# BLE-LORA-Relay-30dbm-v1-1.net
KiCad netlist of a schematic drawn in EAGLE
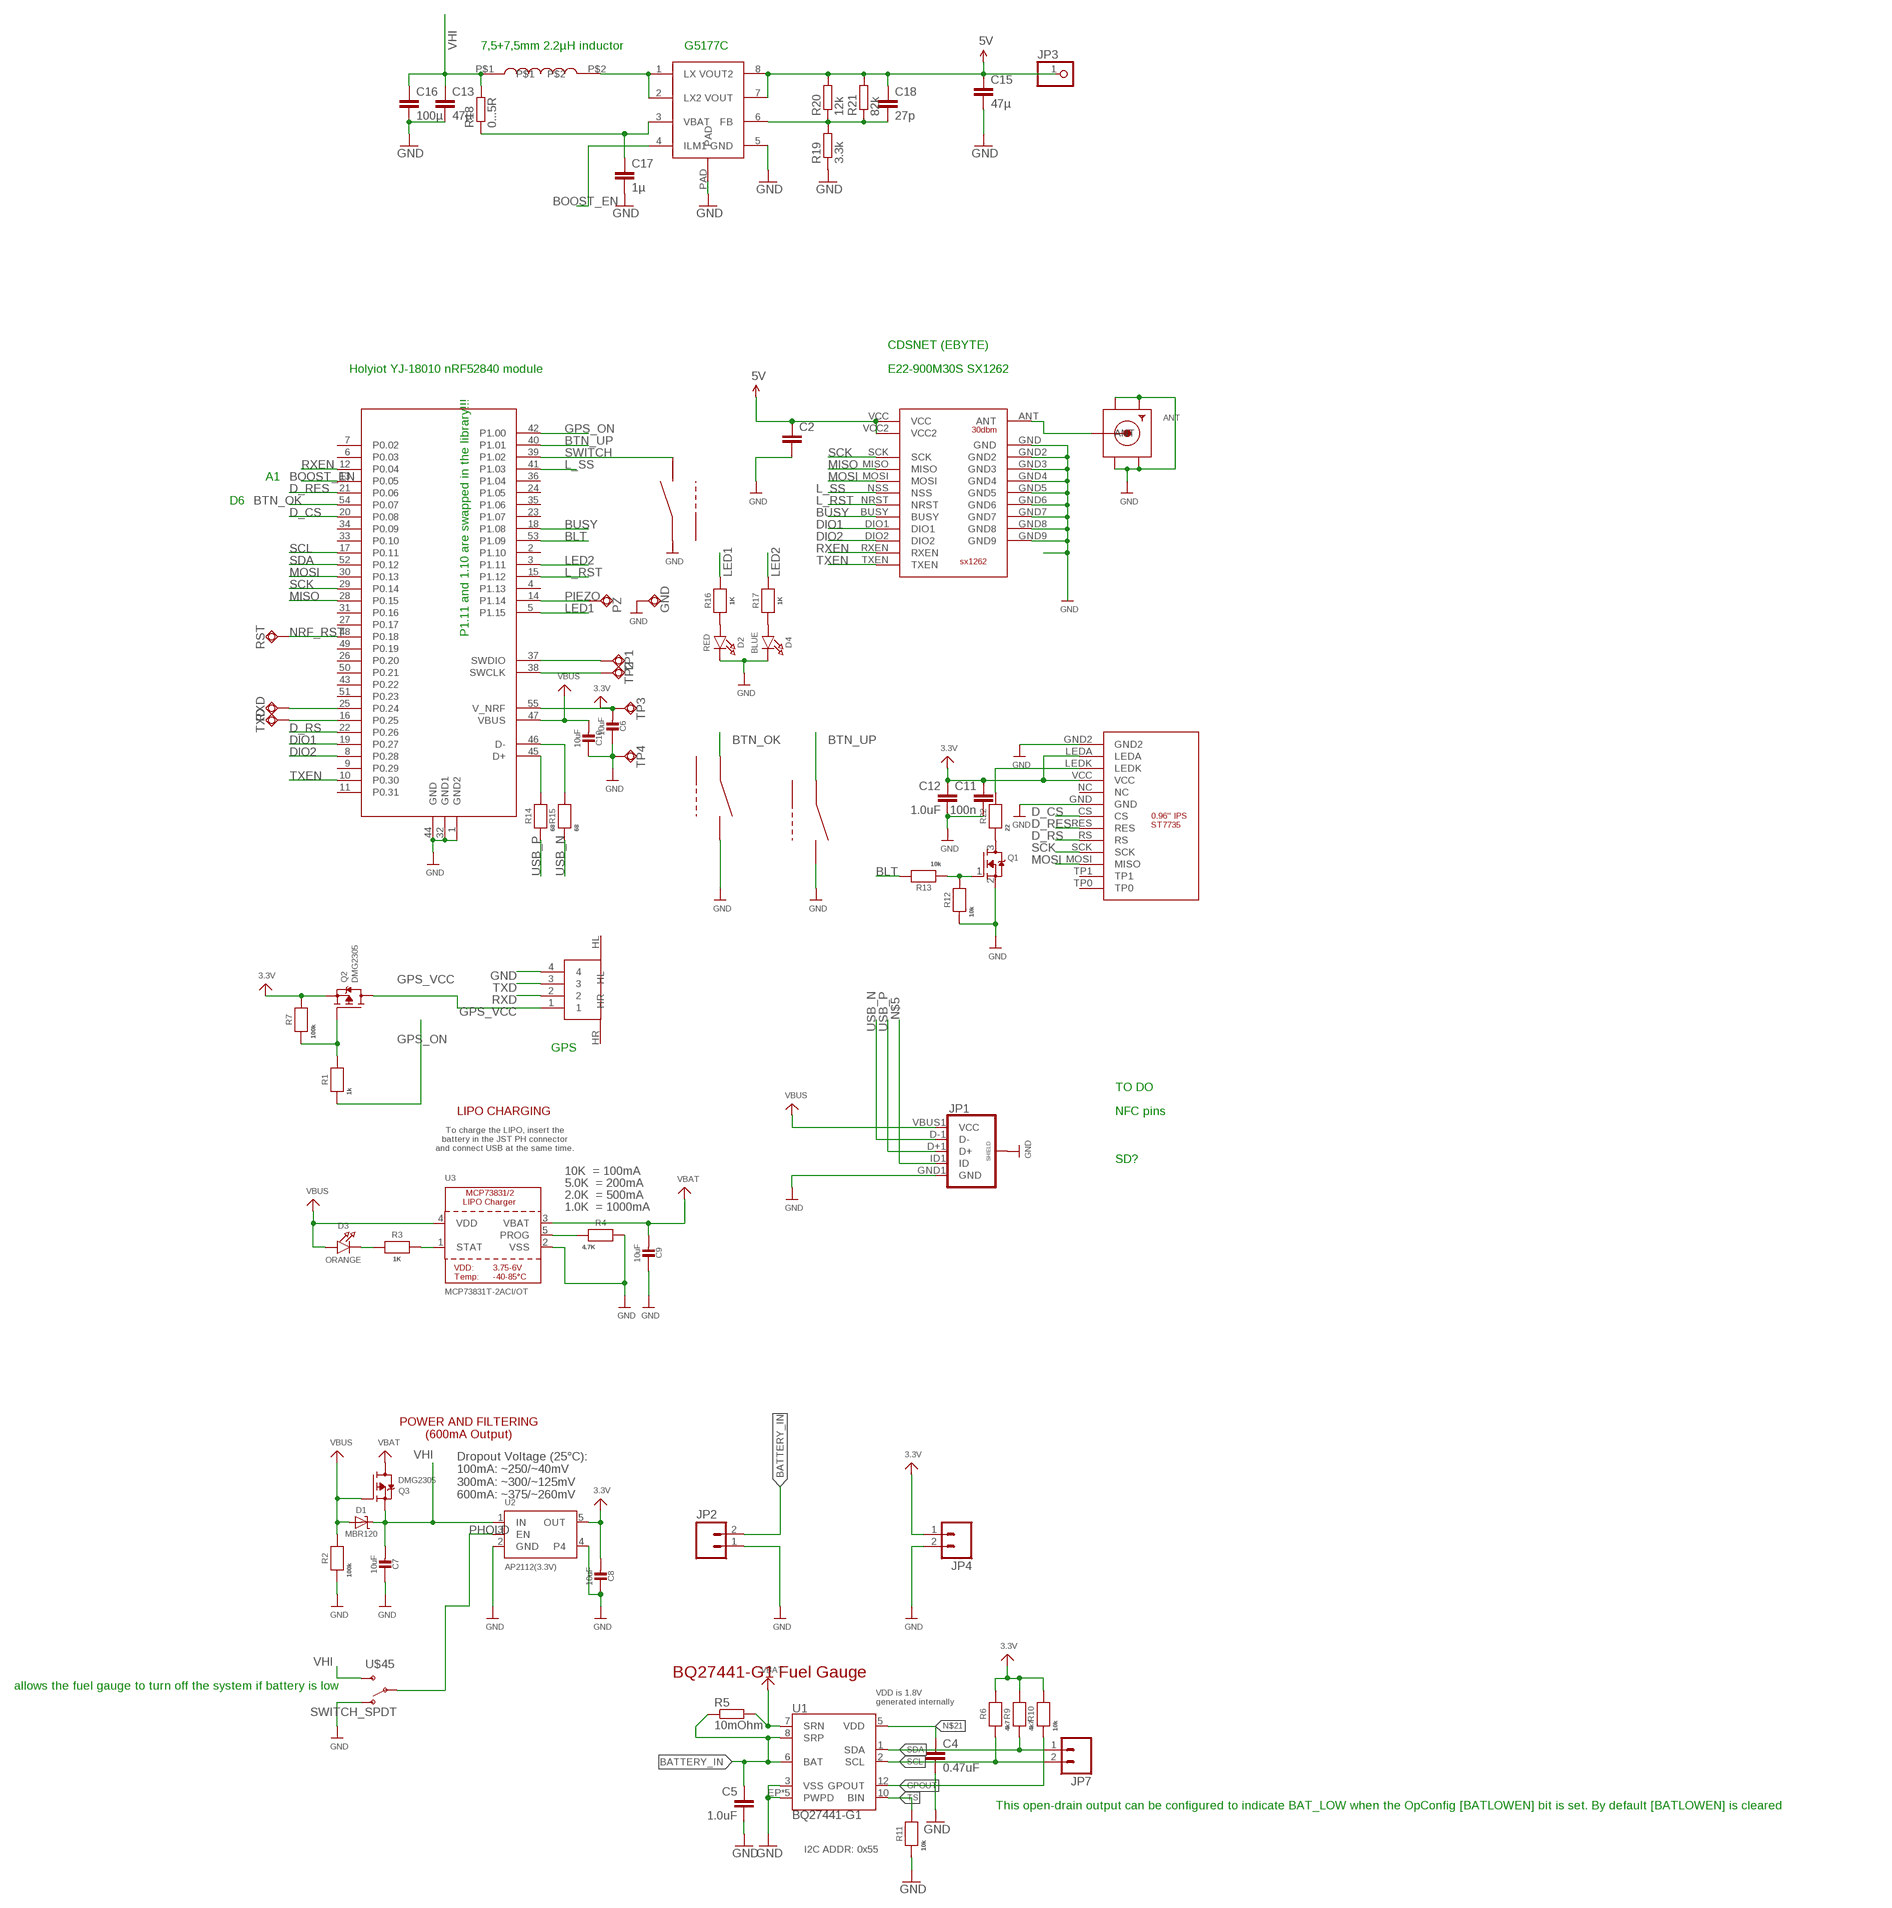
[diagram p0: schematic, sheet 1]

(export (version "E")
  (design (tool "Eeschema 10.0.6"))
  (components
    (comp (ref "ANT")
      (value "SMACONNECTOR_EDGE")
      (footprint "eagle-import:SMA_EDGELAUNCH")
      (libsource (lib "eagle-import") (part "SMACONNECTOR_EDGE"))
    )
    (comp (ref "C2")
      (value "C-EUC1206")
      (footprint "eagle-import:C1206")
      (libsource (lib "eagle-import") (part "C-EUC1206"))
    )
    (comp (ref "C4")
      (value "0.47uF")
      (footprint "eagle-import:0603-CAP")
      (libsource (lib "eagle-import") (part "CAP0603-CAP"))
    )
    (comp (ref "C5")
      (value "1.0uF")
      (footprint "eagle-import:0603-CAP")
      (libsource (lib "eagle-import") (part "1.0UF-16V-10%(0603)"))
    )
    (comp (ref "C6")
      (value "10uF")
      (footprint "eagle-import:0805-NO")
      (libsource (lib "eagle-import") (part "CAP_CERAMIC0805-NOOUTLINE"))
    )
    (comp (ref "C7")
      (value "10uF")
      (footprint "eagle-import:0805-NO")
      (libsource (lib "eagle-import") (part "CAP_CERAMIC0805-NOOUTLINE"))
    )
    (comp (ref "C8")
      (value "10uF")
      (footprint "eagle-import:0805-NO")
      (libsource (lib "eagle-import") (part "CAP_CERAMIC0805-NOOUTLINE"))
    )
    (comp (ref "C9")
      (value "10uF")
      (footprint "eagle-import:0805-NO")
      (libsource (lib "eagle-import") (part "CAP_CERAMIC0805-NOOUTLINE"))
    )
    (comp (ref "C10")
      (value "10uF")
      (footprint "eagle-import:0805-NO")
      (libsource (lib "eagle-import") (part "CAP_CERAMIC0805-NOOUTLINE"))
    )
    (comp (ref "C11")
      (value "100n")
      (footprint "eagle-import:0603-CAP")
      (libsource (lib "eagle-import") (part "1.0UF-16V-10%(0603)"))
    )
    (comp (ref "C12")
      (value "1.0uF")
      (footprint "eagle-import:0603-CAP")
      (libsource (lib "eagle-import") (part "1.0UF-16V-10%(0603)"))
    )
    (comp (ref "C13")
      (value "47µ")
      (footprint "eagle-import:C0805")
      (libsource (lib "eagle-import") (part "C-EUC0805"))
    )
    (comp (ref "C15")
      (value "47µ")
      (footprint "eagle-import:C0805")
      (libsource (lib "eagle-import") (part "C-EUC0805"))
    )
    (comp (ref "C16")
      (value "100µ")
      (footprint "eagle-import:C1206")
      (libsource (lib "eagle-import") (part "C-EUC1206"))
    )
    (comp (ref "C17")
      (value "1µ")
      (footprint "eagle-import:C0603")
      (libsource (lib "eagle-import") (part "C-EUC0603"))
    )
    (comp (ref "C18")
      (value "27p")
      (footprint "eagle-import:C0603")
      (libsource (lib "eagle-import") (part "C-EUC0603"))
    )
    (comp (ref "D1")
      (value "MBR120")
      (footprint "eagle-import:SOD-123")
      (libsource (lib "eagle-import") (part "DIODE-SCHOTTKYSOD-123"))
    )
    (comp (ref "D2")
      (value "RED")
      (footprint "eagle-import:CHIPLED_0805_NOOUTLINE")
      (libsource (lib "eagle-import") (part "LED0805_NOOUTLINE"))
    )
    (comp (ref "D3")
      (value "ORANGE")
      (footprint "eagle-import:CHIPLED_0805_NOOUTLINE")
      (libsource (lib "eagle-import") (part "LED0805_NOOUTLINE"))
    )
    (comp (ref "D4")
      (value "BLUE")
      (footprint "eagle-import:CHIPLED_0805_NOOUTLINE")
      (libsource (lib "eagle-import") (part "LED0805_NOOUTLINE"))
    )
    (comp (ref "DWN")
      (value "LS12T2")
      (footprint "eagle-import:LS12T2")
      (libsource (lib "eagle-import") (part "LS12T2"))
    )
    (comp (ref "DWN1")
      (value "LS12T2")
      (footprint "eagle-import:LS12T2")
      (libsource (lib "eagle-import") (part "LS12T2"))
    )
    (comp (ref "DWN2")
      (value "LS12T2")
      (footprint "eagle-import:LS12T2")
      (libsource (lib "eagle-import") (part "LS12T2"))
    )
    (comp (ref "GND")
      (value "TPSQTP13R")
      (footprint "eagle-import:TP13R")
      (libsource (lib "eagle-import") (part "TPSQTP13R"))
    )
    (comp (ref "JP1")
      (value "USB_MICROB_PLUGCONN-11752")
      (footprint "eagle-import:USB-B-MICRO-SMD_V03")
      (libsource (lib "eagle-import") (part "USB_MICROB_PLUGCONN-11752"))
    )
    (comp (ref "JP2")
      (value "M02PTH")
      (footprint "eagle-import:1X02")
      (libsource (lib "eagle-import") (part "M02PTH"))
    )
    (comp (ref "JP3")
      (value "PINHD-1X1")
      (footprint "eagle-import:1X01")
      (libsource (lib "eagle-import") (part "PINHD-1X1"))
    )
    (comp (ref "JP4")
      (value "M02PTH")
      (footprint "eagle-import:1X02")
      (libsource (lib "eagle-import") (part "M02PTH"))
    )
    (comp (ref "JP7")
      (value "M02PTH")
      (footprint "eagle-import:1X02")
      (libsource (lib "eagle-import") (part "M02PTH"))
    )
    (comp (ref "PZ")
      (value "TPSQTP13R")
      (footprint "eagle-import:TP13R")
      (libsource (lib "eagle-import") (part "TPSQTP13R"))
    )
    (comp (ref "Q1")
      (value "MOSFET-NREFLOW")
      (footprint "eagle-import:SOT23")
      (libsource (lib "eagle-import") (part "MOSFET-NREFLOW"))
    )
    (comp (ref "Q2")
      (value "DMG2305")
      (footprint "eagle-import:SOT23-R")
      (libsource (lib "eagle-import") (part "MOSFET-P"))
    )
    (comp (ref "Q3")
      (value "DMG2305")
      (footprint "eagle-import:SOT23-R")
      (libsource (lib "eagle-import") (part "MOSFET-P"))
    )
    (comp (ref "R1")
      (value "1k")
      (footprint "eagle-import:0603-NO")
      (libsource (lib "eagle-import") (part "RESISTOR_0603_NOOUT"))
    )
    (comp (ref "R2")
      (value "100k")
      (footprint "eagle-import:0603-NO")
      (libsource (lib "eagle-import") (part "RESISTOR_0603_NOOUT"))
    )
    (comp (ref "R3")
      (value "1K")
      (footprint "eagle-import:0603-NO")
      (libsource (lib "eagle-import") (part "RESISTOR_0603_NOOUT"))
    )
    (comp (ref "R4")
      (value "4.7K")
      (footprint "eagle-import:0603-NO")
      (libsource (lib "eagle-import") (part "RESISTOR_0603_NOOUT"))
    )
    (comp (ref "R5")
      (value "10mOhm")
      (footprint "eagle-import:R0805")
      (libsource (lib "eagle-import") (part "R-EU_R0805"))
    )
    (comp (ref "R6")
      (value "4k7")
      (footprint "eagle-import:0603-NO")
      (libsource (lib "eagle-import") (part "RESISTOR_0603_NOOUT"))
    )
    (comp (ref "R7")
      (value "100k")
      (footprint "eagle-import:0603-NO")
      (libsource (lib "eagle-import") (part "RESISTOR_0603_NOOUT"))
    )
    (comp (ref "R9")
      (value "4k7")
      (footprint "eagle-import:0603-NO")
      (libsource (lib "eagle-import") (part "RESISTOR_0603_NOOUT"))
    )
    (comp (ref "R10")
      (value "10k")
      (footprint "eagle-import:0603-NO")
      (libsource (lib "eagle-import") (part "RESISTOR_0603_NOOUT"))
    )
    (comp (ref "R11")
      (value "10k")
      (footprint "eagle-import:0603-NO")
      (libsource (lib "eagle-import") (part "RESISTOR_0603_NOOUT"))
    )
    (comp (ref "R12")
      (value "10k")
      (footprint "eagle-import:0603-NO")
      (libsource (lib "eagle-import") (part "RESISTOR_0603_NOOUT"))
    )
    (comp (ref "R13")
      (value "10k")
      (footprint "eagle-import:0603-NO")
      (libsource (lib "eagle-import") (part "RESISTOR_0603_NOOUT"))
    )
    (comp (ref "R14")
      (value "68")
      (footprint "eagle-import:0603-NO")
      (libsource (lib "eagle-import") (part "RESISTOR_0603_NOOUT"))
    )
    (comp (ref "R15")
      (value "68")
      (footprint "eagle-import:0603-NO")
      (libsource (lib "eagle-import") (part "RESISTOR_0603_NOOUT"))
    )
    (comp (ref "R16")
      (value "1K")
      (footprint "eagle-import:0603-NO")
      (libsource (lib "eagle-import") (part "RESISTOR_0603_NOOUT"))
    )
    (comp (ref "R17")
      (value "1K")
      (footprint "eagle-import:0603-NO")
      (libsource (lib "eagle-import") (part "RESISTOR_0603_NOOUT"))
    )
    (comp (ref "R18")
      (value "0...5R")
      (footprint "eagle-import:R0603")
      (libsource (lib "eagle-import") (part "R-EU_R0603"))
    )
    (comp (ref "R19")
      (value "3.3k")
      (footprint "eagle-import:R0603")
      (libsource (lib "eagle-import") (part "R-EU_R0603"))
    )
    (comp (ref "R20")
      (value "12k")
      (footprint "eagle-import:R0603")
      (libsource (lib "eagle-import") (part "R-EU_R0603"))
    )
    (comp (ref "R21")
      (value "82k")
      (footprint "eagle-import:R0603")
      (libsource (lib "eagle-import") (part "R-EU_R0603"))
    )
    (comp (ref "R22")
      (value "22")
      (footprint "eagle-import:0603-NO")
      (libsource (lib "eagle-import") (part "RESISTOR_0603_NOOUT"))
    )
    (comp (ref "RST")
      (value "TPSQTP13R")
      (footprint "eagle-import:TP13R")
      (libsource (lib "eagle-import") (part "TPSQTP13R"))
    )
    (comp (ref "RXD")
      (value "TPSQTP13R")
      (footprint "eagle-import:TP13R")
      (libsource (lib "eagle-import") (part "TPSQTP13R"))
    )
    (comp (ref "TP1")
      (value "TPSQTP13R")
      (footprint "eagle-import:TP13R")
      (libsource (lib "eagle-import") (part "TPSQTP13R"))
    )
    (comp (ref "TP2")
      (value "TPSQTP13R")
      (footprint "eagle-import:TP13R")
      (libsource (lib "eagle-import") (part "TPSQTP13R"))
    )
    (comp (ref "TP3")
      (value "TPSQTP13R")
      (footprint "eagle-import:TP13R")
      (libsource (lib "eagle-import") (part "TPSQTP13R"))
    )
    (comp (ref "TP4")
      (value "TPSQTP13R")
      (footprint "eagle-import:TP13R")
      (libsource (lib "eagle-import") (part "TPSQTP13R"))
    )
    (comp (ref "TXD")
      (value "TPSQTP13R")
      (footprint "eagle-import:TP13R")
      (libsource (lib "eagle-import") (part "TPSQTP13R"))
    )
    (comp (ref "U$14")
      (value "NRF52840")
      (footprint "eagle-import:NRF52840MOD")
      (libsource (lib "eagle-import") (part "NRF52840"))
    )
    (comp (ref "U$15")
      (value "SX1262-30DBM")
      (footprint "eagle-import:SX1262-30DBM")
      (libsource (lib "eagle-import") (part "SX1262-30DBM"))
    )
    (comp (ref "U$16")
      (value "0.96_IPS")
      (footprint "eagle-import:0.96_IPS")
      (libsource (lib "eagle-import") (part "0.96_IPS"))
    )
    (comp (ref "U$17")
      (value "JST-SH-3")
      (footprint "eagle-import:JST-SH-3")
      (libsource (lib "eagle-import") (part "JST-SH-3"))
    )
    (comp (ref "U$35")
      (value "7.5MM-COIL")
      (footprint "eagle-import:7.5MM_COIL")
      (libsource (lib "eagle-import") (part "7.5MM-COIL"))
    )
    (comp (ref "U$41")
      (value "G5177C")
      (footprint "eagle-import:SO-08")
      (libsource (lib "eagle-import") (part "G5177C"))
    )
    (comp (ref "U$45")
      (value "SWITCH_SPDT")
      (footprint "eagle-import:KPS-1290")
      (libsource (lib "eagle-import") (part "SWITCH_SPDT"))
    )
    (comp (ref "U1")
      (value "BQ27441-G1")
      (footprint "eagle-import:PDSO-N12")
      (libsource (lib "eagle-import") (part "BQ27441-G1"))
    )
    (comp (ref "U2")
      (value "AP2112(3.3V)")
      (footprint "eagle-import:SOT23-5")
      (libsource (lib "eagle-import") (part "VREG_SOT23-5"))
    )
    (comp (ref "U3")
      (value "MCP73831T-2ACI/OT")
      (footprint "eagle-import:SOT23-5")
      (libsource (lib "eagle-import") (part "MCP73831/2"))
    )
  )
  (nets
    (net (code "1") (name "/BLT") (class "Default")
      (node (ref "R13") (pin "2") (pinfunction "2_2") (pintype "passive"))
      (node (ref "U$14") (pin "53") (pinfunction "P1.09_53") (pintype "bidirectional"))
    )
    (net (code "2") (name "/BOOST_EN") (class "Default")
      (node (ref "U$14") (pin "13") (pinfunction "P0.05_13") (pintype "bidirectional"))
      (node (ref "U$41") (pin "4") (pinfunction "ILM1_4") (pintype "bidirectional"))
    )
    (net (code "3") (name "/BTN_OK") (class "Default")
      (node (ref "DWN") (pin "2") (pinfunction "2_2") (pintype "bidirectional"))
      (node (ref "U$14") (pin "54") (pinfunction "P0.07_54") (pintype "bidirectional"))
    )
    (net (code "4") (name "/BTN_UP") (class "Default")
      (node (ref "DWN1") (pin "2") (pinfunction "2_2") (pintype "bidirectional"))
      (node (ref "U$14") (pin "40") (pinfunction "P1.01_40") (pintype "bidirectional"))
    )
    (net (code "5") (name "/BUSY") (class "Default")
      (node (ref "U$14") (pin "18") (pinfunction "P1.08_18") (pintype "bidirectional"))
      (node (ref "U$15") (pin "BUSY") (pinfunction "BUSY_BUSY") (pintype "bidirectional"))
    )
    (net (code "6") (name "/DIO1") (class "Default")
      (node (ref "U$14") (pin "19") (pinfunction "P0.27_19") (pintype "bidirectional"))
      (node (ref "U$15") (pin "DIO1") (pinfunction "DIO1_DIO1") (pintype "bidirectional"))
    )
    (net (code "7") (name "/DIO2") (class "Default")
      (node (ref "U$14") (pin "8") (pinfunction "P0.28_8") (pintype "bidirectional"))
      (node (ref "U$15") (pin "DIO2") (pinfunction "DIO2_DIO2") (pintype "bidirectional"))
    )
    (net (code "8") (name "/D_CS") (class "Default")
      (node (ref "U$14") (pin "20") (pinfunction "P0.08_20") (pintype "bidirectional"))
      (node (ref "U$16") (pin "CS") (pinfunction "CS_CS") (pintype "bidirectional"))
    )
    (net (code "9") (name "/D_RES") (class "Default")
      (node (ref "U$14") (pin "21") (pinfunction "P0.06_21") (pintype "bidirectional"))
      (node (ref "U$16") (pin "RES") (pinfunction "RES_RES") (pintype "bidirectional"))
    )
    (net (code "10") (name "/D_RS") (class "Default")
      (node (ref "U$14") (pin "22") (pinfunction "P0.26_22") (pintype "bidirectional"))
      (node (ref "U$16") (pin "RS") (pinfunction "RS_RS") (pintype "bidirectional"))
    )
    (net (code "11") (name "/GPS_ON") (class "Default")
      (node (ref "R1") (pin "1") (pinfunction "1_1") (pintype "passive"))
      (node (ref "U$14") (pin "42") (pinfunction "P1.00_42") (pintype "bidirectional"))
    )
    (net (code "12") (name "/GPS_VCC") (class "Default")
      (node (ref "Q2") (pin "3") (pinfunction "D_3") (pintype "passive"))
      (node (ref "U$17") (pin "1") (pinfunction "1_1") (pintype "bidirectional"))
    )
    (net (code "13") (name "/LED1") (class "Default")
      (node (ref "R16") (pin "2") (pinfunction "2_2") (pintype "passive"))
      (node (ref "U$14") (pin "5") (pinfunction "P1.15_5") (pintype "bidirectional"))
    )
    (net (code "14") (name "/LED2") (class "Default")
      (node (ref "R17") (pin "2") (pinfunction "2_2") (pintype "passive"))
      (node (ref "U$14") (pin "3") (pinfunction "P1.11_3") (pintype "bidirectional"))
    )
    (net (code "15") (name "/L_RST") (class "Default")
      (node (ref "U$14") (pin "15") (pinfunction "P1.12_15") (pintype "bidirectional"))
      (node (ref "U$15") (pin "NRST") (pinfunction "NRST_NRST") (pintype "bidirectional"))
    )
    (net (code "16") (name "/L_SS") (class "Default")
      (node (ref "U$14") (pin "41") (pinfunction "P1.03_41") (pintype "bidirectional"))
      (node (ref "U$15") (pin "NSS") (pinfunction "NSS_NSS") (pintype "bidirectional"))
    )
    (net (code "17") (name "/MISO") (class "Default")
      (node (ref "U$14") (pin "28") (pinfunction "P0.15_28") (pintype "bidirectional"))
      (node (ref "U$15") (pin "MISO") (pinfunction "MISO_MISO") (pintype "bidirectional"))
    )
    (net (code "18") (name "/MOSI") (class "Default")
      (node (ref "U$14") (pin "30") (pinfunction "P0.13_30") (pintype "bidirectional"))
      (node (ref "U$15") (pin "MOSI") (pinfunction "MOSI_MOSI") (pintype "bidirectional"))
      (node (ref "U$16") (pin "MOSI") (pinfunction "MISO_MOSI") (pintype "bidirectional"))
    )
    (net (code "19") (name "/N$5") (class "Default")
      (node (ref "JP1") (pin "ID1") (pinfunction "ID_ID1") (pintype "bidirectional"))
    )
    (net (code "20") (name "/NRF_RST") (class "Default")
      (node (ref "RST") (pin "TP") (pinfunction "TP_TP") (pintype "input"))
      (node (ref "U$14") (pin "48") (pinfunction "P0.18_48") (pintype "bidirectional"))
    )
    (net (code "21") (name "/PHOLD") (class "Default")
      (node (ref "U$45") (pin "P") (pinfunction "P_P") (pintype "passive"))
      (node (ref "U2") (pin "3") (pinfunction "EN_3") (pintype "input"))
    )
    (net (code "22") (name "/PIEZO") (class "Default")
      (node (ref "PZ") (pin "TP") (pinfunction "TP_TP") (pintype "input"))
      (node (ref "U$14") (pin "14") (pinfunction "P1.14_14") (pintype "bidirectional"))
    )
    (net (code "23") (name "/RXD") (class "Default")
      (node (ref "RXD") (pin "TP") (pinfunction "TP_TP") (pintype "input"))
      (node (ref "U$14") (pin "25") (pinfunction "P0.24_25") (pintype "bidirectional"))
      (node (ref "U$17") (pin "2") (pinfunction "2_2") (pintype "bidirectional"))
    )
    (net (code "24") (name "/RXEN") (class "Default")
      (node (ref "U$14") (pin "12") (pinfunction "P0.04_12") (pintype "bidirectional"))
      (node (ref "U$15") (pin "RXEN") (pinfunction "RXEN_RXEN") (pintype "bidirectional"))
    )
    (net (code "25") (name "/SCK") (class "Default")
      (node (ref "U$14") (pin "29") (pinfunction "P0.14_29") (pintype "bidirectional"))
      (node (ref "U$15") (pin "SCK") (pinfunction "SCK_SCK") (pintype "bidirectional"))
      (node (ref "U$16") (pin "SCK") (pinfunction "SCK_SCK") (pintype "bidirectional"))
    )
    (net (code "26") (name "/SWITCH") (class "Default")
      (node (ref "DWN2") (pin "1") (pinfunction "1_1") (pintype "bidirectional"))
      (node (ref "U$14") (pin "39") (pinfunction "P1.02_39") (pintype "bidirectional"))
    )
    (net (code "27") (name "/TXD") (class "Default")
      (node (ref "TXD") (pin "TP") (pinfunction "TP_TP") (pintype "input"))
      (node (ref "U$14") (pin "16") (pinfunction "P0.25_16") (pintype "bidirectional"))
      (node (ref "U$17") (pin "3") (pinfunction "3_3") (pintype "bidirectional"))
    )
    (net (code "28") (name "/TXEN") (class "Default")
      (node (ref "U$14") (pin "10") (pinfunction "P0.30_10") (pintype "bidirectional"))
      (node (ref "U$15") (pin "TXEN") (pinfunction "TXEN_TXEN") (pintype "bidirectional"))
    )
    (net (code "29") (name "/USB_N") (class "Default")
      (node (ref "JP1") (pin "D-1") (pinfunction "D-_D-1") (pintype "bidirectional"))
      (node (ref "R15") (pin "1") (pinfunction "1_1") (pintype "passive"))
    )
    (net (code "30") (name "/USB_P") (class "Default")
      (node (ref "JP1") (pin "D+1") (pinfunction "D+_D+1") (pintype "bidirectional"))
      (node (ref "R14") (pin "1") (pinfunction "1_1") (pintype "passive"))
    )
    (net (code "31") (name "/VHI") (class "Default")
      (node (ref "C13") (pin "1") (pinfunction "1_1") (pintype "passive"))
      (node (ref "C16") (pin "1") (pinfunction "1_1") (pintype "passive"))
      (node (ref "C7") (pin "2") (pinfunction "2_2") (pintype "passive"))
      (node (ref "D1") (pin "C") (pinfunction "C_C") (pintype "passive"))
      (node (ref "Q3") (pin "2") (pinfunction "S_2") (pintype "passive"))
      (node (ref "R18") (pin "2") (pinfunction "2_2") (pintype "passive"))
      (node (ref "U$35") (pin "P$1") (pinfunction "P$1_P$1") (pintype "bidirectional"))
      (node (ref "U$45") (pin "S") (pinfunction "S_S") (pintype "passive"))
      (node (ref "U2") (pin "1") (pinfunction "IN_1") (pintype "power_in"))
    )
    (net (code "32") (name "3.3V") (class "Default")
      (node (ref "C11") (pin "1") (pinfunction "1_1") (pintype "passive"))
      (node (ref "C12") (pin "1") (pinfunction "1_1") (pintype "passive"))
      (node (ref "C6") (pin "2") (pinfunction "2_2") (pintype "passive"))
      (node (ref "C8") (pin "2") (pinfunction "2_2") (pintype "passive"))
      (node (ref "JP4") (pin "1") (pinfunction "1_1") (pintype "passive"))
      (node (ref "Q2") (pin "2") (pinfunction "S_2") (pintype "passive"))
      (node (ref "R10") (pin "2") (pinfunction "2_2") (pintype "passive"))
      (node (ref "R6") (pin "2") (pinfunction "2_2") (pintype "passive"))
      (node (ref "R7") (pin "2") (pinfunction "2_2") (pintype "passive"))
      (node (ref "R9") (pin "2") (pinfunction "2_2") (pintype "passive"))
      (node (ref "TP3") (pin "TP") (pinfunction "TP_TP") (pintype "input"))
      (node (ref "U$14") (pin "55") (pinfunction "V_NRF_55") (pintype "bidirectional"))
      (node (ref "U$16") (pin "LEDA") (pinfunction "LEDA_LEDA") (pintype "bidirectional"))
      (node (ref "U$16") (pin "VCC") (pinfunction "VCC_VCC") (pintype "bidirectional"))
      (node (ref "U2") (pin "5") (pinfunction "OUT_5") (pintype "power_in"))
    )
    (net (code "33") (name "5V") (class "Default")
      (node (ref "C15") (pin "1") (pinfunction "1_1") (pintype "passive"))
      (node (ref "C18") (pin "1") (pinfunction "1_1") (pintype "passive"))
      (node (ref "C2") (pin "1") (pinfunction "1_1") (pintype "passive"))
      (node (ref "JP3") (pin "1") (pinfunction "1_1") (pintype "passive"))
      (node (ref "R20") (pin "2") (pinfunction "2_2") (pintype "passive"))
      (node (ref "R21") (pin "2") (pinfunction "2_2") (pintype "passive"))
      (node (ref "U$15") (pin "VCC") (pinfunction "VCC_VCC") (pintype "bidirectional"))
      (node (ref "U$15") (pin "VCC2") (pinfunction "VCC2_VCC2") (pintype "bidirectional"))
      (node (ref "U$41") (pin "7") (pinfunction "VOUT_7") (pintype "bidirectional"))
      (node (ref "U$41") (pin "8") (pinfunction "VOUT2_8") (pintype "bidirectional"))
    )
    (net (code "34") (name "BATTERY_IN") (class "Default")
      (node (ref "C5") (pin "1") (pinfunction "1_1") (pintype "passive"))
      (node (ref "JP2") (pin "2") (pinfunction "2_2") (pintype "passive"))
      (node (ref "R5") (pin "1") (pinfunction "1_1") (pintype "passive"))
      (node (ref "U1") (pin "6") (pinfunction "BAT_6") (pintype "bidirectional"))
      (node (ref "U1") (pin "8") (pinfunction "SRP_8") (pintype "bidirectional"))
    )
    (net (code "35") (name "GND") (class "Default")
      (node (ref "ANT") (pin "GND@1") (pinfunction "GND4_GND@1") (pintype "power_in"))
      (node (ref "ANT") (pin "GND@2") (pinfunction "GND3_GND@2") (pintype "power_in"))
      (node (ref "ANT") (pin "GND@3") (pinfunction "GND2_GND@3") (pintype "power_in"))
      (node (ref "ANT") (pin "GND@4") (pinfunction "GND1_GND@4") (pintype "power_in"))
      (node (ref "C10") (pin "1") (pinfunction "1_1") (pintype "passive"))
      (node (ref "C11") (pin "2") (pinfunction "2_2") (pintype "passive"))
      (node (ref "C12") (pin "2") (pinfunction "2_2") (pintype "passive"))
      (node (ref "C13") (pin "2") (pinfunction "2_2") (pintype "passive"))
      (node (ref "C15") (pin "2") (pinfunction "2_2") (pintype "passive"))
      (node (ref "C16") (pin "2") (pinfunction "2_2") (pintype "passive"))
      (node (ref "C17") (pin "2") (pinfunction "2_2") (pintype "passive"))
      (node (ref "C2") (pin "2") (pinfunction "2_2") (pintype "passive"))
      (node (ref "C4") (pin "2") (pinfunction "2_2") (pintype "passive"))
      (node (ref "C5") (pin "2") (pinfunction "2_2") (pintype "passive"))
      (node (ref "C6") (pin "1") (pinfunction "1_1") (pintype "passive"))
      (node (ref "C7") (pin "1") (pinfunction "1_1") (pintype "passive"))
      (node (ref "C8") (pin "1") (pinfunction "1_1") (pintype "passive"))
      (node (ref "C9") (pin "1") (pinfunction "1_1") (pintype "passive"))
      (node (ref "D2") (pin "C") (pinfunction "C_C") (pintype "passive"))
      (node (ref "D4") (pin "C") (pinfunction "C_C") (pintype "passive"))
      (node (ref "DWN") (pin "1") (pinfunction "1_1") (pintype "bidirectional"))
      (node (ref "DWN1") (pin "1") (pinfunction "1_1") (pintype "bidirectional"))
      (node (ref "DWN2") (pin "2") (pinfunction "2_2") (pintype "bidirectional"))
      (node (ref "GND") (pin "TP") (pinfunction "TP_TP") (pintype "input"))
      (node (ref "JP1") (pin "GND1") (pinfunction "GND_GND1") (pintype "bidirectional"))
      (node (ref "JP1") (pin "SHIELD1") (pinfunction "SHIELD_SHIELD1") (pintype "bidirectional"))
      (node (ref "JP1") (pin "SHIELD2") (pinfunction "SHIELD_SHIELD2") (pintype "bidirectional"))
      (node (ref "JP1") (pin "SHIELD3") (pinfunction "SHIELD_SHIELD3") (pintype "bidirectional"))
      (node (ref "JP2") (pin "1") (pinfunction "1_1") (pintype "passive"))
      (node (ref "JP4") (pin "2") (pinfunction "2_2") (pintype "passive"))
      (node (ref "Q1") (pin "2") (pinfunction "S_2") (pintype "bidirectional"))
      (node (ref "R11") (pin "1") (pinfunction "1_1") (pintype "passive"))
      (node (ref "R12") (pin "1") (pinfunction "1_1") (pintype "passive"))
      (node (ref "R19") (pin "1") (pinfunction "1_1") (pintype "passive"))
      (node (ref "R2") (pin "1") (pinfunction "1_1") (pintype "passive"))
      (node (ref "R4") (pin "2") (pinfunction "2_2") (pintype "passive"))
      (node (ref "TP4") (pin "TP") (pinfunction "TP_TP") (pintype "input"))
      (node (ref "U$14") (pin "1") (pinfunction "GND2_1") (pintype "bidirectional"))
      (node (ref "U$14") (pin "32") (pinfunction "GND1_32") (pintype "bidirectional"))
      (node (ref "U$14") (pin "44") (pinfunction "GND_44") (pintype "bidirectional"))
      (node (ref "U$15") (pin "GND") (pinfunction "GND_GND") (pintype "bidirectional"))
      (node (ref "U$15") (pin "GND2") (pinfunction "GND2_GND2") (pintype "bidirectional"))
      (node (ref "U$15") (pin "GND3") (pinfunction "GND3_GND3") (pintype "bidirectional"))
      (node (ref "U$15") (pin "GND4") (pinfunction "GND4_GND4") (pintype "bidirectional"))
      (node (ref "U$15") (pin "GND5") (pinfunction "GND5_GND5") (pintype "bidirectional"))
      (node (ref "U$15") (pin "GND6") (pinfunction "GND6_GND6") (pintype "bidirectional"))
      (node (ref "U$15") (pin "GND7") (pinfunction "GND7_GND7") (pintype "bidirectional"))
      (node (ref "U$15") (pin "GND8") (pinfunction "GND8_GND8") (pintype "bidirectional"))
      (node (ref "U$15") (pin "GND9") (pinfunction "GND9_GND9") (pintype "bidirectional"))
      (node (ref "U$16") (pin "GND") (pinfunction "GND_GND") (pintype "bidirectional"))
      (node (ref "U$16") (pin "GND2") (pinfunction "GND2_GND2") (pintype "bidirectional"))
      (node (ref "U$17") (pin "4") (pinfunction "4_4") (pintype "bidirectional"))
      (node (ref "U$41") (pin "5") (pinfunction "GND_5") (pintype "bidirectional"))
      (node (ref "U$41") (pin "PAD") (pinfunction "PAD_PAD") (pintype "bidirectional"))
      (node (ref "U$45") (pin "O") (pinfunction "O_O") (pintype "passive"))
      (node (ref "U1") (pin "3") (pinfunction "VSS_3") (pintype "bidirectional"))
      (node (ref "U1") (pin "EP") (pinfunction "PWPD_EP") (pintype "bidirectional"))
      (node (ref "U1") (pin "EP1") (pinfunction "PWPD_EP1") (pintype "bidirectional"))
      (node (ref "U1") (pin "EP2") (pinfunction "PWPD_EP2") (pintype "bidirectional"))
      (node (ref "U1") (pin "EP3") (pinfunction "PWPD_EP3") (pintype "bidirectional"))
      (node (ref "U1") (pin "EP4") (pinfunction "PWPD_EP4") (pintype "bidirectional"))
      (node (ref "U2") (pin "2") (pinfunction "GND_2") (pintype "power_in"))
      (node (ref "U2") (pin "4") (pinfunction "P4_4") (pintype "bidirectional"))
      (node (ref "U3") (pin "2") (pinfunction "VSS_2") (pintype "power_in"))
    )
    (net (code "36") (name "GPOUT") (class "Default")
      (node (ref "R10") (pin "1") (pinfunction "1_1") (pintype "passive"))
      (node (ref "U1") (pin "12") (pinfunction "GPOUT_12") (pintype "bidirectional"))
    )
    (net (code "37") (name "N$21") (class "Default")
      (node (ref "C4") (pin "1") (pinfunction "1_1") (pintype "passive"))
      (node (ref "U1") (pin "5") (pinfunction "VDD_5") (pintype "bidirectional"))
    )
    (net (code "38") (name "Net-(ANT-ANT)") (class "Default")
      (node (ref "ANT") (pin "P") (pinfunction "ANT_P") (pintype "bidirectional"))
      (node (ref "U$15") (pin "ANT") (pinfunction "ANT_ANT") (pintype "bidirectional"))
    )
    (net (code "39") (name "Net-(D2-PadA)") (class "Default")
      (node (ref "D2") (pin "A") (pinfunction "A_A") (pintype "passive"))
      (node (ref "R16") (pin "1") (pinfunction "1_1") (pintype "passive"))
    )
    (net (code "40") (name "Net-(D3-PadC)") (class "Default")
      (node (ref "D3") (pin "C") (pinfunction "C_C") (pintype "passive"))
      (node (ref "R3") (pin "1") (pinfunction "1_1") (pintype "passive"))
    )
    (net (code "41") (name "Net-(D4-PadA)") (class "Default")
      (node (ref "D4") (pin "A") (pinfunction "A_A") (pintype "passive"))
      (node (ref "R17") (pin "1") (pinfunction "1_1") (pintype "passive"))
    )
    (net (code "42") (name "Net-(Q1-D)") (class "Default")
      (node (ref "Q1") (pin "3") (pinfunction "D_3") (pintype "bidirectional"))
      (node (ref "R22") (pin "1") (pinfunction "1_1") (pintype "passive"))
    )
    (net (code "43") (name "Net-(Q1-G)") (class "Default")
      (node (ref "Q1") (pin "1") (pinfunction "G_1") (pintype "bidirectional"))
      (node (ref "R12") (pin "2") (pinfunction "2_2") (pintype "passive"))
      (node (ref "R13") (pin "1") (pinfunction "1_1") (pintype "passive"))
    )
    (net (code "44") (name "Net-(Q2-G)") (class "Default")
      (node (ref "Q2") (pin "1") (pinfunction "G_1") (pintype "passive"))
      (node (ref "R1") (pin "2") (pinfunction "2_2") (pintype "passive"))
      (node (ref "R7") (pin "1") (pinfunction "1_1") (pintype "passive"))
    )
    (net (code "45") (name "Net-(R22-Pad2)") (class "Default")
      (node (ref "R22") (pin "2") (pinfunction "2_2") (pintype "passive"))
      (node (ref "U$16") (pin "LEDK") (pinfunction "LEDK_LEDK") (pintype "bidirectional"))
    )
    (net (code "46") (name "Net-(U$14-D+)") (class "Default")
      (node (ref "R14") (pin "2") (pinfunction "2_2") (pintype "passive"))
      (node (ref "U$14") (pin "45") (pinfunction "D+_45") (pintype "bidirectional"))
    )
    (net (code "47") (name "Net-(U$14-D-)") (class "Default")
      (node (ref "R15") (pin "2") (pinfunction "2_2") (pintype "passive"))
      (node (ref "U$14") (pin "46") (pinfunction "D-_46") (pintype "bidirectional"))
    )
    (net (code "48") (name "Net-(U$14-SWCLK)") (class "Default")
      (node (ref "TP2") (pin "TP") (pinfunction "TP_TP") (pintype "input"))
      (node (ref "U$14") (pin "38") (pinfunction "SWCLK_38") (pintype "bidirectional"))
    )
    (net (code "49") (name "Net-(U$14-SWDIO)") (class "Default")
      (node (ref "TP1") (pin "TP") (pinfunction "TP_TP") (pintype "input"))
      (node (ref "U$14") (pin "37") (pinfunction "SWDIO_37") (pintype "bidirectional"))
    )
    (net (code "50") (name "Net-(U$41-FB)") (class "Default")
      (node (ref "C18") (pin "2") (pinfunction "2_2") (pintype "passive"))
      (node (ref "R19") (pin "2") (pinfunction "2_2") (pintype "passive"))
      (node (ref "R20") (pin "1") (pinfunction "1_1") (pintype "passive"))
      (node (ref "R21") (pin "1") (pinfunction "1_1") (pintype "passive"))
      (node (ref "U$41") (pin "6") (pinfunction "FB_6") (pintype "bidirectional"))
    )
    (net (code "51") (name "Net-(U$41-LX)") (class "Default")
      (node (ref "U$35") (pin "P$2") (pinfunction "P$2_P$2") (pintype "bidirectional"))
      (node (ref "U$41") (pin "1") (pinfunction "LX_1") (pintype "bidirectional"))
      (node (ref "U$41") (pin "2") (pinfunction "LX2_2") (pintype "bidirectional"))
    )
    (net (code "52") (name "Net-(U$41-VBAT)") (class "Default")
      (node (ref "C17") (pin "1") (pinfunction "1_1") (pintype "passive"))
      (node (ref "R18") (pin "1") (pinfunction "1_1") (pintype "passive"))
      (node (ref "U$41") (pin "3") (pinfunction "VBAT_3") (pintype "bidirectional"))
    )
    (net (code "53") (name "Net-(U3-PROG)") (class "Default")
      (node (ref "R4") (pin "1") (pinfunction "1_1") (pintype "passive"))
      (node (ref "U3") (pin "5") (pinfunction "PROG_5") (pintype "input"))
    )
    (net (code "54") (name "Net-(U3-STAT)") (class "Default")
      (node (ref "R3") (pin "2") (pinfunction "2_2") (pintype "passive"))
      (node (ref "U3") (pin "1") (pinfunction "STAT_1") (pintype "output"))
    )
    (net (code "55") (name "SCL") (class "Default")
      (node (ref "JP7") (pin "2") (pinfunction "2_2") (pintype "passive"))
      (node (ref "R6") (pin "1") (pinfunction "1_1") (pintype "passive"))
      (node (ref "U$14") (pin "17") (pinfunction "P0.11_17") (pintype "bidirectional"))
      (node (ref "U1") (pin "2") (pinfunction "SCL_2") (pintype "bidirectional"))
    )
    (net (code "56") (name "SDA") (class "Default")
      (node (ref "JP7") (pin "1") (pinfunction "1_1") (pintype "passive"))
      (node (ref "R9") (pin "1") (pinfunction "1_1") (pintype "passive"))
      (node (ref "U$14") (pin "52") (pinfunction "P0.12_52") (pintype "bidirectional"))
      (node (ref "U1") (pin "1") (pinfunction "SDA_1") (pintype "bidirectional"))
    )
    (net (code "57") (name "TS") (class "Default")
      (node (ref "R11") (pin "2") (pinfunction "2_2") (pintype "passive"))
      (node (ref "U1") (pin "10") (pinfunction "BIN_10") (pintype "bidirectional"))
    )
    (net (code "58") (name "VBAT") (class "Default")
      (node (ref "C9") (pin "2") (pinfunction "2_2") (pintype "passive"))
      (node (ref "Q3") (pin "3") (pinfunction "D_3") (pintype "passive"))
      (node (ref "R5") (pin "2") (pinfunction "2_2") (pintype "passive"))
      (node (ref "U1") (pin "7") (pinfunction "SRN_7") (pintype "bidirectional"))
      (node (ref "U3") (pin "3") (pinfunction "VBAT_3") (pintype "power_in"))
    )
    (net (code "59") (name "VBUS") (class "Default")
      (node (ref "C10") (pin "2") (pinfunction "2_2") (pintype "passive"))
      (node (ref "D1") (pin "A") (pinfunction "A_A") (pintype "passive"))
      (node (ref "D3") (pin "A") (pinfunction "A_A") (pintype "passive"))
      (node (ref "JP1") (pin "VBUS1") (pinfunction "VCC_VBUS1") (pintype "bidirectional"))
      (node (ref "Q3") (pin "1") (pinfunction "G_1") (pintype "passive"))
      (node (ref "R2") (pin "2") (pinfunction "2_2") (pintype "passive"))
      (node (ref "U$14") (pin "47") (pinfunction "VBUS_47") (pintype "bidirectional"))
      (node (ref "U3") (pin "4") (pinfunction "VDD_4") (pintype "power_in"))
    )
    (net (code "60") (name "unconnected-(DWN-FRM-PadFRAME)") (class "Default")
      (node (ref "DWN") (pin "FRAME") (pinfunction "FRM_FRAME") (pintype "bidirectional"))
    )
    (net (code "61") (name "unconnected-(DWN1-FRM-PadFRAME)") (class "Default")
      (node (ref "DWN1") (pin "FRAME") (pinfunction "FRM_FRAME") (pintype "bidirectional"))
    )
    (net (code "62") (name "unconnected-(DWN2-FRM-PadFRAME)") (class "Default")
      (node (ref "DWN2") (pin "FRAME") (pinfunction "FRM_FRAME") (pintype "bidirectional"))
    )
    (net (code "63") (name "unconnected-(U$14-P0.02-Pad7)") (class "Default")
      (node (ref "U$14") (pin "7") (pinfunction "P0.02_7") (pintype "bidirectional"))
    )
    (net (code "64") (name "unconnected-(U$14-P0.03-Pad6)") (class "Default")
      (node (ref "U$14") (pin "6") (pinfunction "P0.03_6") (pintype "bidirectional"))
    )
    (net (code "65") (name "unconnected-(U$14-P0.09-Pad34)") (class "Default")
      (node (ref "U$14") (pin "34") (pinfunction "P0.09_34") (pintype "bidirectional"))
    )
    (net (code "66") (name "unconnected-(U$14-P0.10-Pad33)") (class "Default")
      (node (ref "U$14") (pin "33") (pinfunction "P0.10_33") (pintype "bidirectional"))
    )
    (net (code "67") (name "unconnected-(U$14-P0.16-Pad31)") (class "Default")
      (node (ref "U$14") (pin "31") (pinfunction "P0.16_31") (pintype "bidirectional"))
    )
    (net (code "68") (name "unconnected-(U$14-P0.17-Pad27)") (class "Default")
      (node (ref "U$14") (pin "27") (pinfunction "P0.17_27") (pintype "bidirectional"))
    )
    (net (code "69") (name "unconnected-(U$14-P0.19-Pad49)") (class "Default")
      (node (ref "U$14") (pin "49") (pinfunction "P0.19_49") (pintype "bidirectional"))
    )
    (net (code "70") (name "unconnected-(U$14-P0.20-Pad26)") (class "Default")
      (node (ref "U$14") (pin "26") (pinfunction "P0.20_26") (pintype "bidirectional"))
    )
    (net (code "71") (name "unconnected-(U$14-P0.21-Pad50)") (class "Default")
      (node (ref "U$14") (pin "50") (pinfunction "P0.21_50") (pintype "bidirectional"))
    )
    (net (code "72") (name "unconnected-(U$14-P0.22-Pad43)") (class "Default")
      (node (ref "U$14") (pin "43") (pinfunction "P0.22_43") (pintype "bidirectional"))
    )
    (net (code "73") (name "unconnected-(U$14-P0.23-Pad51)") (class "Default")
      (node (ref "U$14") (pin "51") (pinfunction "P0.23_51") (pintype "bidirectional"))
    )
    (net (code "74") (name "unconnected-(U$14-P0.29-Pad9)") (class "Default")
      (node (ref "U$14") (pin "9") (pinfunction "P0.29_9") (pintype "bidirectional"))
    )
    (net (code "75") (name "unconnected-(U$14-P0.31-Pad11)") (class "Default")
      (node (ref "U$14") (pin "11") (pinfunction "P0.31_11") (pintype "bidirectional"))
    )
    (net (code "76") (name "unconnected-(U$14-P1.04-Pad36)") (class "Default")
      (node (ref "U$14") (pin "36") (pinfunction "P1.04_36") (pintype "bidirectional"))
    )
    (net (code "77") (name "unconnected-(U$14-P1.05-Pad24)") (class "Default")
      (node (ref "U$14") (pin "24") (pinfunction "P1.05_24") (pintype "bidirectional"))
    )
    (net (code "78") (name "unconnected-(U$14-P1.06-Pad35)") (class "Default")
      (node (ref "U$14") (pin "35") (pinfunction "P1.06_35") (pintype "bidirectional"))
    )
    (net (code "79") (name "unconnected-(U$14-P1.07-Pad23)") (class "Default")
      (node (ref "U$14") (pin "23") (pinfunction "P1.07_23") (pintype "bidirectional"))
    )
    (net (code "80") (name "unconnected-(U$14-P1.10-Pad2)") (class "Default")
      (node (ref "U$14") (pin "2") (pinfunction "P1.10_2") (pintype "bidirectional"))
    )
    (net (code "81") (name "unconnected-(U$14-P1.13-Pad4)") (class "Default")
      (node (ref "U$14") (pin "4") (pinfunction "P1.13_4") (pintype "bidirectional"))
    )
    (net (code "82") (name "unconnected-(U$16-PadNC)") (class "Default")
      (node (ref "U$16") (pin "NC") (pinfunction "NC_NC") (pintype "bidirectional"))
    )
    (net (code "83") (name "unconnected-(U$16-PadTP0)") (class "Default")
      (node (ref "U$16") (pin "TP0") (pinfunction "TP0_TP0") (pintype "bidirectional"))
    )
    (net (code "84") (name "unconnected-(U$16-PadTP1)") (class "Default")
      (node (ref "U$16") (pin "TP1") (pinfunction "TP1_TP1") (pintype "bidirectional"))
    )
    (net (code "85") (name "unconnected-(U$17-PadHL)") (class "Default")
      (node (ref "U$17") (pin "HL") (pinfunction "HL_HL") (pintype "bidirectional"))
    )
    (net (code "86") (name "unconnected-(U$17-PadHR)") (class "Default")
      (node (ref "U$17") (pin "HR") (pinfunction "HR_HR") (pintype "bidirectional"))
    )
  )
)
